# PT_Sensor.net
KiCad netlist of a schematic drawn in Altium Designer
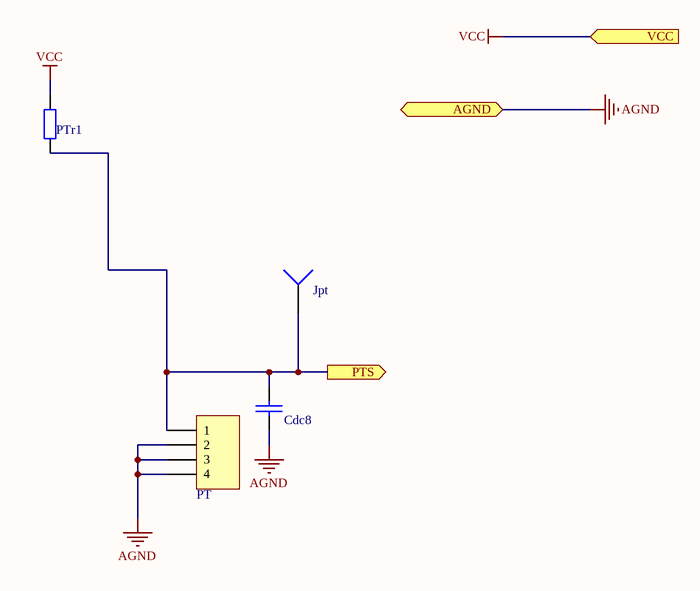
[diagram p0: PT_Sensor.SchDoc]

(export (version "E")
  (design (tool "Eeschema 10.0.6"))
  (components
    (comp (ref "Cdc8")
      (value "47nF")
      (footprint "ECE-CAPC2012-0805SM")
      (description "CAP CER 47nF 50V X7R SM0805")
      (libsource (lib "Capacitos$") (part "CAP000522"))
    )
    (comp (ref "Jpt")
      (value "TEST PIN")
      (footprint "ECE-HDR1TH")
      (libsource (lib "Connectors$") (part "CON000017"))
    )
    (comp (ref "PT")
      (value "4 Way")
      (footprint "ECE-600104STTH")
      (description "HEADER POLARISED 4WAY TH")
      (libsource (lib "Connectors$") (part "CON000003"))
    )
    (comp (ref "PTr1")
      (value "39K")
      (footprint "ECE-RESC1608-0603SM")
      (description "RES CER 39K 1608 SM")
      (libsource (lib "Resistors$") (part "RES000157"))
    )
  )
  (nets
    (net (code "1") (name "/PTS") (class "Default")
      (node (ref "Cdc8") (pin "1") (pinfunction "1_1") (pintype "passive"))
      (node (ref "Jpt") (pin "1") (pinfunction "1_1") (pintype "passive"))
      (node (ref "PT") (pin "1") (pinfunction "1_1") (pintype "passive"))
      (node (ref "PTr1") (pin "1") (pinfunction "1_1") (pintype "passive"))
    )
    (net (code "2") (name "AGND") (class "Default")
      (node (ref "Cdc8") (pin "2") (pinfunction "2_2") (pintype "passive"))
      (node (ref "PT") (pin "2") (pinfunction "2_2") (pintype "passive"))
      (node (ref "PT") (pin "3") (pinfunction "3_3") (pintype "passive"))
      (node (ref "PT") (pin "4") (pinfunction "4_4") (pintype "passive"))
    )
    (net (code "3") (name "VCC") (class "Default")
      (node (ref "PTr1") (pin "2") (pinfunction "2_2") (pintype "passive"))
    )
  )
)
